# supplies.net
KiCad netlist of a schematic drawn in Altium Designer
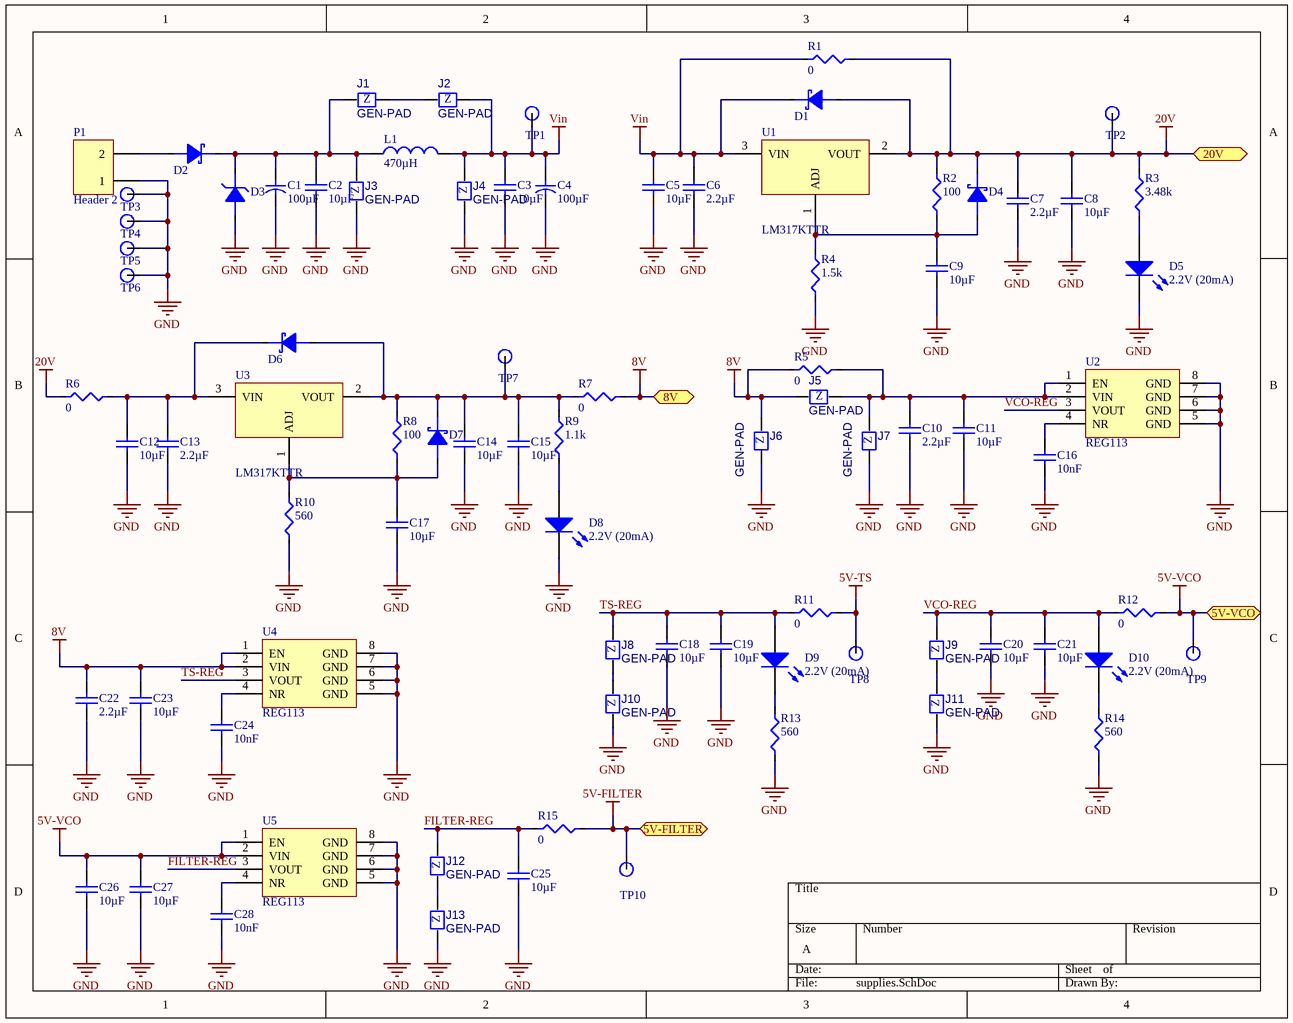
[diagram p0: supplies.SchDoc]

(export (version "E")
  (design (tool "Eeschema 10.0.6"))
  (components
    (comp (ref "C1")
      (value "100µF")
      (footprint "Radial-SMD-8x10mm")
      (description "CAP-POL")
      (fields (field (name "EE PART NUMBER") "EE-CAP-00001") (field (name "VOLTAGE") "50V"))
      (libsource (lib "EE") (part "CAP-POL"))
    )
    (comp (ref "C2")
      (value "10µF")
      (footprint "C0805-1.25MM")
      (description "Capacitor")
      (fields (field (name "EE PART NUMBER") "EE-CAP-00002") (field (name "VOLTAGE") "35V"))
      (libsource (lib "EE") (part "CAP"))
    )
    (comp (ref "C3")
      (value "10µF")
      (footprint "C0805-1.25MM")
      (description "Capacitor")
      (fields (field (name "EE PART NUMBER") "EE-CAP-00002") (field (name "VOLTAGE") "35V"))
      (libsource (lib "EE") (part "CAP"))
    )
    (comp (ref "C4")
      (value "100µF")
      (footprint "Radial-SMD-8x10mm")
      (description "CAP-POL")
      (fields (field (name "EE PART NUMBER") "EE-CAP-00001") (field (name "VOLTAGE") "50V"))
      (libsource (lib "EE") (part "CAP-POL"))
    )
    (comp (ref "C5")
      (value "10µF")
      (footprint "C0805-1.25MM")
      (description "Capacitor")
      (fields (field (name "EE PART NUMBER") "EE-CAP-00002") (field (name "VOLTAGE") "35V"))
      (libsource (lib "EE") (part "CAP"))
    )
    (comp (ref "C6")
      (value "2.2µF")
      (footprint "0402-0.55mm")
      (description "Capacitor")
      (fields (field (name "EE PART NUMBER") "EE-CAP-00003") (field (name "VOLTAGE") "35V"))
      (libsource (lib "EE") (part "CAP"))
    )
    (comp (ref "C7")
      (value "2.2µF")
      (footprint "0402-0.55mm")
      (description "Capacitor")
      (fields (field (name "EE PART NUMBER") "EE-CAP-00003") (field (name "VOLTAGE") "35V"))
      (libsource (lib "EE") (part "CAP"))
    )
    (comp (ref "C8")
      (value "10µF")
      (footprint "C0805-1.25MM")
      (description "Capacitor")
      (fields (field (name "EE PART NUMBER") "EE-CAP-00002") (field (name "VOLTAGE") "35V"))
      (libsource (lib "EE") (part "CAP"))
    )
    (comp (ref "C9")
      (value "10µF")
      (footprint "C0805-1.25MM")
      (description "Capacitor")
      (fields (field (name "EE PART NUMBER") "EE-CAP-00002") (field (name "VOLTAGE") "35V"))
      (libsource (lib "EE") (part "CAP"))
    )
    (comp (ref "C10")
      (value "2.2µF")
      (footprint "0402-0.55mm")
      (description "Capacitor")
      (fields (field (name "EE PART NUMBER") "EE-CAP-00003") (field (name "VOLTAGE") "35V"))
      (libsource (lib "EE") (part "CAP"))
    )
    (comp (ref "C11")
      (value "10µF")
      (footprint "C0805-1.25MM")
      (description "Capacitor")
      (fields (field (name "EE PART NUMBER") "EE-CAP-00002") (field (name "VOLTAGE") "35V"))
      (libsource (lib "EE") (part "CAP"))
    )
    (comp (ref "C12")
      (value "10µF")
      (footprint "C0805-1.25MM")
      (description "Capacitor")
      (fields (field (name "EE PART NUMBER") "EE-CAP-00002") (field (name "VOLTAGE") "35V"))
      (libsource (lib "EE") (part "CAP"))
    )
    (comp (ref "C13")
      (value "2.2µF")
      (footprint "0402-0.55mm")
      (description "Capacitor")
      (fields (field (name "EE PART NUMBER") "EE-CAP-00003") (field (name "VOLTAGE") "35V"))
      (libsource (lib "EE") (part "CAP"))
    )
    (comp (ref "C14")
      (value "10µF")
      (footprint "0402-0.55mm")
      (description "Capacitor")
      (fields (field (name "EE PART NUMBER") "EE-CAP-00009") (field (name "VOLTAGE") "10V"))
      (libsource (lib "EE") (part "CAP"))
    )
    (comp (ref "C15")
      (value "10µF")
      (footprint "0402-0.55mm")
      (description "Capacitor")
      (fields (field (name "EE PART NUMBER") "EE-CAP-00009") (field (name "VOLTAGE") "10V"))
      (libsource (lib "EE") (part "CAP"))
    )
    (comp (ref "C16")
      (value "10nF")
      (footprint "C0805-1.25MM")
      (description "Capacitor")
      (fields (field (name "EE PART NUMBER") "EE-CAP-00010") (field (name "VOLTAGE") "50V"))
      (libsource (lib "EE") (part "CAP"))
    )
    (comp (ref "C17")
      (value "10µF")
      (footprint "C0805-1.25MM")
      (description "Capacitor")
      (fields (field (name "EE PART NUMBER") "EE-CAP-00002") (field (name "VOLTAGE") "35V"))
      (libsource (lib "EE") (part "CAP"))
    )
    (comp (ref "C18")
      (value "10µF")
      (footprint "0402-0.55mm")
      (description "Capacitor")
      (fields (field (name "EE PART NUMBER") "EE-CAP-00004") (field (name "VOLTAGE") "10V"))
      (libsource (lib "EE") (part "CAP"))
    )
    (comp (ref "C19")
      (value "10µF")
      (footprint "0402-0.55mm")
      (description "Capacitor")
      (fields (field (name "EE PART NUMBER") "EE-CAP-00004") (field (name "VOLTAGE") "10V"))
      (libsource (lib "EE") (part "CAP"))
    )
    (comp (ref "C20")
      (value "10µF")
      (footprint "0402-0.55mm")
      (description "Capacitor")
      (fields (field (name "EE PART NUMBER") "EE-CAP-00004") (field (name "VOLTAGE") "10V"))
      (libsource (lib "EE") (part "CAP"))
    )
    (comp (ref "C21")
      (value "10µF")
      (footprint "0402-0.55mm")
      (description "Capacitor")
      (fields (field (name "EE PART NUMBER") "EE-CAP-00004") (field (name "VOLTAGE") "10V"))
      (libsource (lib "EE") (part "CAP"))
    )
    (comp (ref "C22")
      (value "2.2µF")
      (footprint "0402-0.55mm")
      (description "Capacitor")
      (fields (field (name "EE PART NUMBER") "EE-CAP-00003") (field (name "VOLTAGE") "35V"))
      (libsource (lib "EE") (part "CAP"))
    )
    (comp (ref "C23")
      (value "10µF")
      (footprint "C0805-1.25MM")
      (description "Capacitor")
      (fields (field (name "EE PART NUMBER") "EE-CAP-00002") (field (name "VOLTAGE") "35V"))
      (libsource (lib "EE") (part "CAP"))
    )
    (comp (ref "C24")
      (value "10nF")
      (footprint "C0805-1.25MM")
      (description "Capacitor")
      (fields (field (name "EE PART NUMBER") "EE-CAP-00010") (field (name "VOLTAGE") "50V"))
      (libsource (lib "EE") (part "CAP"))
    )
    (comp (ref "C25")
      (value "10µF")
      (footprint "0402-0.55mm")
      (description "Capacitor")
      (fields (field (name "EE PART NUMBER") "EE-CAP-00004") (field (name "VOLTAGE") "10V"))
      (libsource (lib "EE") (part "CAP"))
    )
    (comp (ref "C26")
      (value "10µF")
      (footprint "0402-0.55mm")
      (description "Capacitor")
      (fields (field (name "EE PART NUMBER") "EE-CAP-00004") (field (name "VOLTAGE") "10V"))
      (libsource (lib "EE") (part "CAP"))
    )
    (comp (ref "C27")
      (value "10µF")
      (footprint "0402-0.55mm")
      (description "Capacitor")
      (fields (field (name "EE PART NUMBER") "EE-CAP-00004") (field (name "VOLTAGE") "10V"))
      (libsource (lib "EE") (part "CAP"))
    )
    (comp (ref "C28")
      (value "10nF")
      (footprint "C0805-1.25MM")
      (description "Capacitor")
      (fields (field (name "EE PART NUMBER") "EE-CAP-00010") (field (name "VOLTAGE") "50V"))
      (libsource (lib "EE") (part "CAP"))
    )
    (comp (ref "D1")
      (value "SCHOTTKY")
      (footprint "SOD-123f")
      (description "Schottky Diode")
      (fields (field (name "EE PART NUMBER") "EE-DIODE-00002") (field (name "VOLTAGE") "30V"))
      (libsource (lib "EE") (part "SCHOTTKY"))
    )
    (comp (ref "D2")
      (value "SCHOTTKY")
      (footprint "SOD-123f:SOD-123f")
      (description "Schottky Diode")
      (fields (field (name "EE PART NUMBER") "EE-DIODE-00002") (field (name "VOLTAGE") "30V"))
      (libsource (lib "EE") (part "SCHOTTKY"))
    )
    (comp (ref "D3")
      (value "ZENER")
      (footprint "DO-214AA")
      (fields
        (field (name "EE PART NUMBER") "EE-DIODE-00004")
        (field (name "VOLTAGE") "25V")
        (field (name "MANUFACTURER") "Micro")
      )
      (libsource (lib "EE") (part "ZENER"))
    )
    (comp (ref "D4")
      (value "SCHOTTKY")
      (footprint "SOD-123f:SOD-123f")
      (description "Schottky Diode")
      (fields (field (name "EE PART NUMBER") "EE-DIODE-00002") (field (name "VOLTAGE") "30V"))
      (libsource (lib "EE") (part "SCHOTTKY"))
    )
    (comp (ref "D5")
      (value "2.2V (20mA)")
      (footprint "0805-LED")
      (description "LED")
      (fields (field (name "EE PART NUMBER") "EE-DIODE-00003") (field (name "VOLTAGE") "2.2V"))
      (libsource (lib "EE") (part "LED"))
    )
    (comp (ref "D6")
      (value "SCHOTTKY")
      (footprint "SOD-123f")
      (description "Schottky Diode")
      (fields (field (name "EE PART NUMBER") "EE-DIODE-00002") (field (name "VOLTAGE") "30V"))
      (libsource (lib "EE") (part "SCHOTTKY"))
    )
    (comp (ref "D7")
      (value "SCHOTTKY")
      (footprint "SOD-123f")
      (description "Schottky Diode")
      (fields (field (name "EE PART NUMBER") "EE-DIODE-00002") (field (name "VOLTAGE") "30V"))
      (libsource (lib "EE") (part "SCHOTTKY"))
    )
    (comp (ref "D8")
      (value "2.2V (20mA)")
      (footprint "0805-LED")
      (description "LED")
      (fields (field (name "EE PART NUMBER") "EE-DIODE-00003") (field (name "VOLTAGE") "2.2V"))
      (libsource (lib "EE") (part "LED"))
    )
    (comp (ref "D9")
      (value "2.2V (20mA)")
      (footprint "0805-LED")
      (description "LED")
      (fields (field (name "EE PART NUMBER") "EE-DIODE-00003") (field (name "VOLTAGE") "2.2V"))
      (libsource (lib "EE") (part "LED"))
    )
    (comp (ref "D10")
      (value "2.2V (20mA)")
      (footprint "0805-LED")
      (description "LED")
      (fields (field (name "EE PART NUMBER") "EE-DIODE-00003") (field (name "VOLTAGE") "2.2V"))
      (libsource (lib "EE") (part "LED"))
    )
    (comp (ref "J1")
      (value "GEN-PAD")
      (footprint "0805-DNP")
      (description "Generic Component")
      (fields (field (name "EE PART NUMBER") "EE-GEN-00001"))
      (libsource (lib "EE") (part "GEN-PAD"))
    )
    (comp (ref "J2")
      (value "GEN-PAD")
      (footprint "0805-DNP")
      (description "Generic Component")
      (fields (field (name "EE PART NUMBER") "EE-GEN-00001"))
      (libsource (lib "EE") (part "GEN-PAD"))
    )
    (comp (ref "J3")
      (value "GEN-PAD")
      (footprint "0805-DNP")
      (description "Generic Component")
      (fields (field (name "EE PART NUMBER") "EE-GEN-00001"))
      (libsource (lib "EE") (part "GEN-PAD"))
    )
    (comp (ref "J4")
      (value "GEN-PAD")
      (footprint "0805-DNP")
      (description "Generic Component")
      (fields (field (name "EE PART NUMBER") "EE-GEN-00001"))
      (libsource (lib "EE") (part "GEN-PAD"))
    )
    (comp (ref "J5")
      (value "GEN-PAD")
      (footprint "0805-DNP")
      (description "Generic Component")
      (fields (field (name "EE PART NUMBER") "EE-GEN-00001"))
      (libsource (lib "EE") (part "GEN-PAD"))
    )
    (comp (ref "J6")
      (value "GEN-PAD")
      (footprint "0805-DNP")
      (description "Generic Component")
      (fields (field (name "EE PART NUMBER") "EE-GEN-00001"))
      (libsource (lib "EE") (part "GEN-PAD"))
    )
    (comp (ref "J7")
      (value "GEN-PAD")
      (footprint "0805-DNP")
      (description "Generic Component")
      (fields (field (name "EE PART NUMBER") "EE-GEN-00001"))
      (libsource (lib "EE") (part "GEN-PAD"))
    )
    (comp (ref "J8")
      (value "GEN-PAD")
      (footprint "0805-DNP")
      (description "Generic Component")
      (fields (field (name "EE PART NUMBER") "EE-GEN-00001"))
      (libsource (lib "EE") (part "GEN-PAD"))
    )
    (comp (ref "J9")
      (value "GEN-PAD")
      (footprint "0805-DNP")
      (description "Generic Component")
      (fields (field (name "EE PART NUMBER") "EE-GEN-00001"))
      (libsource (lib "EE") (part "GEN-PAD"))
    )
    (comp (ref "J10")
      (value "GEN-PAD")
      (footprint "0805-DNP")
      (description "Generic Component")
      (fields (field (name "EE PART NUMBER") "EE-GEN-00001"))
      (libsource (lib "EE") (part "GEN-PAD"))
    )
    (comp (ref "J11")
      (value "GEN-PAD")
      (footprint "0805-DNP")
      (description "Generic Component")
      (fields (field (name "EE PART NUMBER") "EE-GEN-00001"))
      (libsource (lib "EE") (part "GEN-PAD"))
    )
    (comp (ref "J12")
      (value "GEN-PAD")
      (footprint "0805-DNP")
      (description "Generic Component")
      (fields (field (name "EE PART NUMBER") "EE-GEN-00001"))
      (libsource (lib "EE") (part "GEN-PAD"))
    )
    (comp (ref "J13")
      (value "GEN-PAD")
      (footprint "0805-DNP")
      (description "Generic Component")
      (fields (field (name "EE PART NUMBER") "EE-GEN-00001"))
      (libsource (lib "EE") (part "GEN-PAD"))
    )
    (comp (ref "L1")
      (value "470µH")
      (footprint "7447709471")
      (description "Inductor")
      (fields (field (name "EE PART NUMBER") "EE-L-00002") (field (name "TOLERANCE") "±20%"))
      (libsource (lib "EE") (part "L"))
    )
    (comp (ref "P1")
      (value "Header 2")
      (footprint "HDR1X2")
      (fields
        (field (name "EM PART NUMBER") "EM-CON-00012")
        (field (name "MANUFACTURER") "3M")
        (field (name "MANUFACTURER PART NUMBER") "961102-6404-AR")
      )
      (libsource (lib "EM") (part "HDR-2"))
    )
    (comp (ref "R1")
      (value "0")
      (footprint "0805-0.45MM")
      (fields
        (field (name "EM PART NUMBER") "EM-RES-01617")
        (field (name "POWER") "0.33W")
        (field (name "MANUFACTURER") "Vishay")
      )
      (libsource (lib "EM") (part "RES"))
    )
    (comp (ref "R2")
      (value "100")
      (footprint "0805-0.45MM")
      (fields
        (field (name "EM PART NUMBER") "EM-RES-01370")
        (field (name "TOLERANCE") "1%")
        (field (name "POWER") "0.125W")
      )
      (libsource (lib "EM") (part "RES"))
    )
    (comp (ref "R3")
      (value "3.48k")
      (footprint "0805-0.45MM")
      (fields
        (field (name "EM PART NUMBER") "EM-RES-01196")
        (field (name "TOLERANCE") "1%")
        (field (name "POWER") "0.125W")
      )
      (libsource (lib "EM") (part "RES"))
    )
    (comp (ref "R4")
      (value "1.5k")
      (footprint "0805-0.45MM")
      (fields
        (field (name "EM PART NUMBER") "EM-RES-01238")
        (field (name "TOLERANCE") "1%")
        (field (name "POWER") "0.125W")
      )
      (libsource (lib "EM") (part "RES"))
    )
    (comp (ref "R5")
      (value "0")
      (footprint "0805-0.45MM")
      (fields
        (field (name "EM PART NUMBER") "EM-RES-01617")
        (field (name "POWER") "0.33W")
        (field (name "MANUFACTURER") "Vishay")
      )
      (libsource (lib "EM") (part "RES"))
    )
    (comp (ref "R6")
      (value "0")
      (footprint "0805-0.45MM")
      (fields
        (field (name "EM PART NUMBER") "EM-RES-01617")
        (field (name "POWER") "0.33W")
        (field (name "MANUFACTURER") "Vishay")
      )
      (libsource (lib "EM") (part "RES"))
    )
    (comp (ref "R7")
      (value "0")
      (footprint "0805-0.45MM")
      (fields
        (field (name "EM PART NUMBER") "EM-RES-01617")
        (field (name "POWER") "0.33W")
        (field (name "MANUFACTURER") "Vishay")
      )
      (libsource (lib "EM") (part "RES"))
    )
    (comp (ref "R8")
      (value "100")
      (footprint "0805-0.45MM")
      (fields
        (field (name "EM PART NUMBER") "EM-RES-01370")
        (field (name "TOLERANCE") "1%")
        (field (name "POWER") "0.125W")
      )
      (libsource (lib "EM") (part "RES"))
    )
    (comp (ref "R9")
      (value "1.1k")
      (footprint "0805-0.45MM")
      (fields
        (field (name "EM PART NUMBER") "EM-RES-01252")
        (field (name "TOLERANCE") "1%")
        (field (name "POWER") "0.125W")
      )
      (libsource (lib "EM") (part "RES"))
    )
    (comp (ref "R10")
      (value "560")
      (footprint "0805-0.45MM")
      (fields
        (field (name "EM PART NUMBER") "EM-RES-01285")
        (field (name "TOLERANCE") "1%")
        (field (name "POWER") "0.125W")
      )
      (libsource (lib "EM") (part "RES"))
    )
    (comp (ref "R11")
      (value "0")
      (footprint "0805-0.45MM")
      (fields
        (field (name "EM PART NUMBER") "EM-RES-01617")
        (field (name "POWER") "0.33W")
        (field (name "MANUFACTURER") "Vishay")
      )
      (libsource (lib "EM") (part "RES"))
    )
    (comp (ref "R12")
      (value "0")
      (footprint "0805-0.45MM")
      (fields
        (field (name "EM PART NUMBER") "EM-RES-01617")
        (field (name "POWER") "0.33W")
        (field (name "MANUFACTURER") "Vishay")
      )
      (libsource (lib "EM") (part "RES"))
    )
    (comp (ref "R13")
      (value "560")
      (footprint "0805-0.45MM")
      (fields
        (field (name "EM PART NUMBER") "EM-RES-01285")
        (field (name "TOLERANCE") "1%")
        (field (name "POWER") "0.125W")
      )
      (libsource (lib "EM") (part "RES"))
    )
    (comp (ref "R14")
      (value "560")
      (footprint "0805-0.45MM")
      (fields
        (field (name "EM PART NUMBER") "EM-RES-01285")
        (field (name "TOLERANCE") "1%")
        (field (name "POWER") "0.125W")
      )
      (libsource (lib "EM") (part "RES"))
    )
    (comp (ref "R15")
      (value "0")
      (footprint "0805-0.45MM")
      (fields
        (field (name "EM PART NUMBER") "EM-RES-01617")
        (field (name "POWER") "0.33W")
        (field (name "MANUFACTURER") "Vishay")
      )
      (libsource (lib "EM") (part "RES"))
    )
    (comp (ref "TP1")
      (value "TP-LOOP")
      (footprint "TP-LOOP")
      (fields (field (name "EM PART NUMBER") "EM-TP-00006"))
      (libsource (lib "EM") (part "TP-LOOP"))
    )
    (comp (ref "TP2")
      (value "TP-LOOP")
      (footprint "TP-LOOP")
      (fields (field (name "EM PART NUMBER") "EM-TP-00006"))
      (libsource (lib "EM") (part "TP-LOOP"))
    )
    (comp (ref "TP3")
      (value "TP-LOOP")
      (footprint "TP-LOOP")
      (fields (field (name "EM PART NUMBER") "EM-TP-00006"))
      (libsource (lib "EM") (part "TP-LOOP"))
    )
    (comp (ref "TP4")
      (value "TP-LOOP")
      (footprint "TP-LOOP")
      (fields (field (name "EM PART NUMBER") "EM-TP-00006"))
      (libsource (lib "EM") (part "TP-LOOP"))
    )
    (comp (ref "TP5")
      (value "TP-LOOP")
      (footprint "TP-LOOP")
      (fields (field (name "EM PART NUMBER") "EM-TP-00006"))
      (libsource (lib "EM") (part "TP-LOOP"))
    )
    (comp (ref "TP6")
      (value "TP-LOOP")
      (footprint "TP-LOOP")
      (fields (field (name "EM PART NUMBER") "EM-TP-00006"))
      (libsource (lib "EM") (part "TP-LOOP"))
    )
    (comp (ref "TP7")
      (value "TP-LOOP")
      (footprint "TP-LOOP")
      (fields (field (name "EM PART NUMBER") "EM-TP-00006"))
      (libsource (lib "EM") (part "TP-LOOP"))
    )
    (comp (ref "TP8")
      (value "TP-LOOP")
      (footprint "TP-LOOP")
      (fields (field (name "EM PART NUMBER") "EM-TP-00006"))
      (libsource (lib "EM") (part "TP-LOOP"))
    )
    (comp (ref "TP9")
      (value "TP-LOOP")
      (footprint "TP-LOOP")
      (fields (field (name "EM PART NUMBER") "EM-TP-00006"))
      (libsource (lib "EM") (part "TP-LOOP"))
    )
    (comp (ref "TP10")
      (value "TP-LOOP")
      (footprint "TP-LOOP")
      (fields (field (name "EM PART NUMBER") "EM-TP-00006"))
      (libsource (lib "EM") (part "TP-LOOP"))
    )
    (comp (ref "U1")
      (value "LM317KTTR")
      (footprint "TO-263-4")
      (fields (field (name "EE PART NUMBER") "EE-VREG-00004") (field (name "MANUFACTURER") "TI"))
      (libsource (lib "EE") (part "LM317"))
    )
    (comp (ref "U2")
      (value "REG113")
      (footprint "MSOP8")
      (fields
        (field (name "EE PART NUMBER") "EE-VREG-00002")
        (field (name "MANUFACTURER") "TI")
        (field (name "MANUFACTURER PART NUMBER") "REG113EA-5/250")
      )
      (libsource (lib "EE") (part "REG113"))
    )
    (comp (ref "U3")
      (value "LM317KTTR")
      (footprint "TO-263-4")
      (fields (field (name "EE PART NUMBER") "EE-VREG-00004") (field (name "MANUFACTURER") "TI"))
      (libsource (lib "EE") (part "LM317"))
    )
    (comp (ref "U4")
      (value "REG113")
      (footprint "MSOP8")
      (fields
        (field (name "EE PART NUMBER") "EE-VREG-00002")
        (field (name "MANUFACTURER") "TI")
        (field (name "MANUFACTURER PART NUMBER") "REG113EA-5/250")
      )
      (libsource (lib "EE") (part "REG113"))
    )
    (comp (ref "U5")
      (value "REG113")
      (footprint "MSOP8")
      (fields
        (field (name "EE PART NUMBER") "EE-VREG-00003")
        (field (name "MANUFACTURER") "TI")
        (field (name "MANUFACTURER PART NUMBER") "REG113EA-2.5/2K5")
      )
      (libsource (lib "EE") (part "REG113"))
    )
  )
  (nets
    (net (code "1") (name "/FILTER-REG") (class "Default")
      (node (ref "C25") (pin "1") (pinfunction "1_1") (pintype "passive"))
      (node (ref "J12") (pin "1") (pinfunction "1_1") (pintype "passive"))
      (node (ref "R15") (pin "1") (pinfunction "1_1") (pintype "passive"))
      (node (ref "U5") (pin "3") (pinfunction "VOUT_3") (pintype "passive"))
    )
    (net (code "2") (name "/TS-REG") (class "Default")
      (node (ref "C18") (pin "2") (pinfunction "2_2") (pintype "passive"))
      (node (ref "C19") (pin "2") (pinfunction "2_2") (pintype "passive"))
      (node (ref "D9") (pin "A") (pinfunction "A_A") (pintype "passive"))
      (node (ref "J8") (pin "1") (pinfunction "1_1") (pintype "passive"))
      (node (ref "R11") (pin "1") (pinfunction "1_1") (pintype "passive"))
      (node (ref "U4") (pin "3") (pinfunction "VOUT_3") (pintype "passive"))
    )
    (net (code "3") (name "/VCO-REG") (class "Default")
      (node (ref "C20") (pin "2") (pinfunction "2_2") (pintype "passive"))
      (node (ref "C21") (pin "2") (pinfunction "2_2") (pintype "passive"))
      (node (ref "D10") (pin "A") (pinfunction "A_A") (pintype "passive"))
      (node (ref "J9") (pin "1") (pinfunction "1_1") (pintype "passive"))
      (node (ref "R12") (pin "2") (pinfunction "2_2") (pintype "passive"))
      (node (ref "U2") (pin "3") (pinfunction "VOUT_3") (pintype "passive"))
    )
    (net (code "4") (name "5V-FILTER") (class "Default")
      (node (ref "R15") (pin "2") (pinfunction "2_2") (pintype "passive"))
      (node (ref "TP10") (pin "0") (pinfunction "0_0") (pintype "passive"))
    )
    (net (code "5") (name "5V-TS") (class "Default")
      (node (ref "R11") (pin "2") (pinfunction "2_2") (pintype "passive"))
      (node (ref "TP8") (pin "0") (pinfunction "0_0") (pintype "passive"))
    )
    (net (code "6") (name "5V-VCO") (class "Default")
      (node (ref "C26") (pin "1") (pinfunction "1_1") (pintype "passive"))
      (node (ref "C27") (pin "1") (pinfunction "1_1") (pintype "passive"))
      (node (ref "R12") (pin "1") (pinfunction "1_1") (pintype "passive"))
      (node (ref "TP9") (pin "0") (pinfunction "0_0") (pintype "passive"))
      (node (ref "U5") (pin "1") (pinfunction "EN_1") (pintype "passive"))
      (node (ref "U5") (pin "2") (pinfunction "VIN_2") (pintype "passive"))
    )
    (net (code "7") (name "8V") (class "Default")
      (node (ref "C22") (pin "2") (pinfunction "2_2") (pintype "passive"))
      (node (ref "C23") (pin "2") (pinfunction "2_2") (pintype "passive"))
      (node (ref "J5") (pin "2") (pinfunction "2_2") (pintype "passive"))
      (node (ref "J6") (pin "1") (pinfunction "1_1") (pintype "passive"))
      (node (ref "R5") (pin "1") (pinfunction "1_1") (pintype "passive"))
      (node (ref "R7") (pin "2") (pinfunction "2_2") (pintype "passive"))
      (node (ref "U4") (pin "1") (pinfunction "EN_1") (pintype "passive"))
      (node (ref "U4") (pin "2") (pinfunction "VIN_2") (pintype "passive"))
    )
    (net (code "8") (name "20V") (class "Default")
      (node (ref "C7") (pin "2") (pinfunction "2_2") (pintype "passive"))
      (node (ref "C8") (pin "2") (pinfunction "2_2") (pintype "passive"))
      (node (ref "D1") (pin "A") (pinfunction "A_A") (pintype "passive"))
      (node (ref "D4") (pin "C") (pinfunction "C_C") (pintype "passive"))
      (node (ref "R1") (pin "2") (pinfunction "2_2") (pintype "passive"))
      (node (ref "R2") (pin "2") (pinfunction "2_2") (pintype "passive"))
      (node (ref "R3") (pin "2") (pinfunction "2_2") (pintype "passive"))
      (node (ref "R6") (pin "1") (pinfunction "1_1") (pintype "passive"))
      (node (ref "TP2") (pin "0") (pinfunction "0_0") (pintype "passive"))
      (node (ref "U1") (pin "2") (pinfunction "VOUT_2") (pintype "power_in"))
    )
    (net (code "9") (name "GND") (class "Default")
      (node (ref "C1") (pin "1") (pinfunction "1_1") (pintype "passive"))
      (node (ref "C10") (pin "1") (pinfunction "1_1") (pintype "passive"))
      (node (ref "C11") (pin "1") (pinfunction "1_1") (pintype "passive"))
      (node (ref "C12") (pin "1") (pinfunction "1_1") (pintype "passive"))
      (node (ref "C13") (pin "1") (pinfunction "1_1") (pintype "passive"))
      (node (ref "C14") (pin "1") (pinfunction "1_1") (pintype "passive"))
      (node (ref "C15") (pin "1") (pinfunction "1_1") (pintype "passive"))
      (node (ref "C16") (pin "1") (pinfunction "1_1") (pintype "passive"))
      (node (ref "C17") (pin "1") (pinfunction "1_1") (pintype "passive"))
      (node (ref "C18") (pin "1") (pinfunction "1_1") (pintype "passive"))
      (node (ref "C19") (pin "1") (pinfunction "1_1") (pintype "passive"))
      (node (ref "C2") (pin "1") (pinfunction "1_1") (pintype "passive"))
      (node (ref "C20") (pin "1") (pinfunction "1_1") (pintype "passive"))
      (node (ref "C21") (pin "1") (pinfunction "1_1") (pintype "passive"))
      (node (ref "C22") (pin "1") (pinfunction "1_1") (pintype "passive"))
      (node (ref "C23") (pin "1") (pinfunction "1_1") (pintype "passive"))
      (node (ref "C24") (pin "1") (pinfunction "1_1") (pintype "passive"))
      (node (ref "C25") (pin "2") (pinfunction "2_2") (pintype "passive"))
      (node (ref "C26") (pin "2") (pinfunction "2_2") (pintype "passive"))
      (node (ref "C27") (pin "2") (pinfunction "2_2") (pintype "passive"))
      (node (ref "C28") (pin "1") (pinfunction "1_1") (pintype "passive"))
      (node (ref "C3") (pin "1") (pinfunction "1_1") (pintype "passive"))
      (node (ref "C4") (pin "1") (pinfunction "1_1") (pintype "passive"))
      (node (ref "C5") (pin "1") (pinfunction "1_1") (pintype "passive"))
      (node (ref "C6") (pin "1") (pinfunction "1_1") (pintype "passive"))
      (node (ref "C7") (pin "1") (pinfunction "1_1") (pintype "passive"))
      (node (ref "C8") (pin "1") (pinfunction "1_1") (pintype "passive"))
      (node (ref "C9") (pin "1") (pinfunction "1_1") (pintype "passive"))
      (node (ref "D3") (pin "1") (pinfunction "A_1") (pintype "passive"))
      (node (ref "D5") (pin "C") (pinfunction "C_C") (pintype "passive"))
      (node (ref "D8") (pin "C") (pinfunction "C_C") (pintype "passive"))
      (node (ref "J10") (pin "2") (pinfunction "2_2") (pintype "passive"))
      (node (ref "J11") (pin "2") (pinfunction "2_2") (pintype "passive"))
      (node (ref "J13") (pin "2") (pinfunction "2_2") (pintype "passive"))
      (node (ref "J3") (pin "2") (pinfunction "2_2") (pintype "passive"))
      (node (ref "J4") (pin "2") (pinfunction "2_2") (pintype "passive"))
      (node (ref "J6") (pin "2") (pinfunction "2_2") (pintype "passive"))
      (node (ref "J7") (pin "2") (pinfunction "2_2") (pintype "passive"))
      (node (ref "P1") (pin "1") (pinfunction "1_1") (pintype "passive"))
      (node (ref "R10") (pin "1") (pinfunction "1_1") (pintype "passive"))
      (node (ref "R13") (pin "1") (pinfunction "1_1") (pintype "passive"))
      (node (ref "R14") (pin "1") (pinfunction "1_1") (pintype "passive"))
      (node (ref "R4") (pin "1") (pinfunction "1_1") (pintype "passive"))
      (node (ref "TP3") (pin "0") (pinfunction "0_0") (pintype "passive"))
      (node (ref "TP4") (pin "0") (pinfunction "0_0") (pintype "passive"))
      (node (ref "TP5") (pin "0") (pinfunction "0_0") (pintype "passive"))
      (node (ref "TP6") (pin "0") (pinfunction "0_0") (pintype "passive"))
      (node (ref "U2") (pin "5") (pinfunction "GND_5") (pintype "passive"))
      (node (ref "U2") (pin "6") (pinfunction "GND_6") (pintype "passive"))
      (node (ref "U2") (pin "7") (pinfunction "GND_7") (pintype "passive"))
      (node (ref "U2") (pin "8") (pinfunction "GND_8") (pintype "passive"))
      (node (ref "U4") (pin "5") (pinfunction "GND_5") (pintype "passive"))
      (node (ref "U4") (pin "6") (pinfunction "GND_6") (pintype "passive"))
      (node (ref "U4") (pin "7") (pinfunction "GND_7") (pintype "passive"))
      (node (ref "U4") (pin "8") (pinfunction "GND_8") (pintype "passive"))
      (node (ref "U5") (pin "5") (pinfunction "GND_5") (pintype "passive"))
      (node (ref "U5") (pin "6") (pinfunction "GND_6") (pintype "passive"))
      (node (ref "U5") (pin "7") (pinfunction "GND_7") (pintype "passive"))
      (node (ref "U5") (pin "8") (pinfunction "GND_8") (pintype "passive"))
    )
    (net (code "10") (name "Net-(D2-PadA)") (class "Default")
      (node (ref "D2") (pin "A") (pinfunction "A_A") (pintype "passive"))
      (node (ref "P1") (pin "2") (pinfunction "2_2") (pintype "passive"))
    )
    (net (code "11") (name "Net-(D3-C)") (class "Default")
      (node (ref "C1") (pin "2") (pinfunction "2_2") (pintype "passive"))
      (node (ref "C2") (pin "2") (pinfunction "2_2") (pintype "passive"))
      (node (ref "D2") (pin "C") (pinfunction "C_C") (pintype "passive"))
      (node (ref "D3") (pin "2") (pinfunction "C_2") (pintype "passive"))
      (node (ref "J1") (pin "2") (pinfunction "2_2") (pintype "passive"))
      (node (ref "J3") (pin "1") (pinfunction "1_1") (pintype "passive"))
      (node (ref "L1") (pin "1") (pinfunction "1_1") (pintype "passive"))
    )
    (net (code "12") (name "Net-(D5-PadA)") (class "Default")
      (node (ref "D5") (pin "A") (pinfunction "A_A") (pintype "passive"))
      (node (ref "R3") (pin "1") (pinfunction "1_1") (pintype "passive"))
    )
    (net (code "13") (name "Net-(D8-PadA)") (class "Default")
      (node (ref "D8") (pin "A") (pinfunction "A_A") (pintype "passive"))
      (node (ref "R9") (pin "1") (pinfunction "1_1") (pintype "passive"))
    )
    (net (code "14") (name "Net-(D9-PadC)") (class "Default")
      (node (ref "D9") (pin "C") (pinfunction "C_C") (pintype "passive"))
      (node (ref "R13") (pin "2") (pinfunction "2_2") (pintype "passive"))
    )
    (net (code "15") (name "Net-(D10-PadC)") (class "Default")
      (node (ref "D10") (pin "C") (pinfunction "C_C") (pintype "passive"))
      (node (ref "R14") (pin "2") (pinfunction "2_2") (pintype "passive"))
    )
    (net (code "16") (name "Net-(J1-Pad1)") (class "Default")
      (node (ref "J1") (pin "1") (pinfunction "1_1") (pintype "passive"))
      (node (ref "J2") (pin "2") (pinfunction "2_2") (pintype "passive"))
    )
    (net (code "17") (name "Net-(J10-Pad1)") (class "Default")
      (node (ref "J10") (pin "1") (pinfunction "1_1") (pintype "passive"))
      (node (ref "J8") (pin "2") (pinfunction "2_2") (pintype "passive"))
    )
    (net (code "18") (name "Net-(J11-Pad1)") (class "Default")
      (node (ref "J11") (pin "1") (pinfunction "1_1") (pintype "passive"))
      (node (ref "J9") (pin "2") (pinfunction "2_2") (pintype "passive"))
    )
    (net (code "19") (name "Net-(J12-Pad2)") (class "Default")
      (node (ref "J12") (pin "2") (pinfunction "2_2") (pintype "passive"))
      (node (ref "J13") (pin "1") (pinfunction "1_1") (pintype "passive"))
    )
    (net (code "20") (name "Net-(U1-ADJ)") (class "Default")
      (node (ref "C9") (pin "2") (pinfunction "2_2") (pintype "passive"))
      (node (ref "D4") (pin "A") (pinfunction "A_A") (pintype "passive"))
      (node (ref "R2") (pin "1") (pinfunction "1_1") (pintype "passive"))
      (node (ref "R4") (pin "2") (pinfunction "2_2") (pintype "passive"))
      (node (ref "U1") (pin "1") (pinfunction "ADJ_1") (pintype "power_in"))
    )
    (net (code "21") (name "Net-(U2-EN)") (class "Default")
      (node (ref "C10") (pin "2") (pinfunction "2_2") (pintype "passive"))
      (node (ref "C11") (pin "2") (pinfunction "2_2") (pintype "passive"))
      (node (ref "J5") (pin "1") (pinfunction "1_1") (pintype "passive"))
      (node (ref "J7") (pin "1") (pinfunction "1_1") (pintype "passive"))
      (node (ref "R5") (pin "2") (pinfunction "2_2") (pintype "passive"))
      (node (ref "U2") (pin "1") (pinfunction "EN_1") (pintype "passive"))
      (node (ref "U2") (pin "2") (pinfunction "VIN_2") (pintype "passive"))
    )
    (net (code "22") (name "Net-(U2-NR)") (class "Default")
      (node (ref "C16") (pin "2") (pinfunction "2_2") (pintype "passive"))
      (node (ref "U2") (pin "4") (pinfunction "NR_4") (pintype "passive"))
    )
    (net (code "23") (name "Net-(U3-ADJ)") (class "Default")
      (node (ref "C17") (pin "2") (pinfunction "2_2") (pintype "passive"))
      (node (ref "D7") (pin "A") (pinfunction "A_A") (pintype "passive"))
      (node (ref "R10") (pin "2") (pinfunction "2_2") (pintype "passive"))
      (node (ref "R8") (pin "1") (pinfunction "1_1") (pintype "passive"))
      (node (ref "U3") (pin "1") (pinfunction "ADJ_1") (pintype "power_in"))
    )
    (net (code "24") (name "Net-(U3-VIN)") (class "Default")
      (node (ref "C12") (pin "2") (pinfunction "2_2") (pintype "passive"))
      (node (ref "C13") (pin "2") (pinfunction "2_2") (pintype "passive"))
      (node (ref "D6") (pin "C") (pinfunction "C_C") (pintype "passive"))
      (node (ref "R6") (pin "2") (pinfunction "2_2") (pintype "passive"))
      (node (ref "U3") (pin "3") (pinfunction "VIN_3") (pintype "power_in"))
    )
    (net (code "25") (name "Net-(U3-VOUT)") (class "Default")
      (node (ref "C14") (pin "2") (pinfunction "2_2") (pintype "passive"))
      (node (ref "C15") (pin "2") (pinfunction "2_2") (pintype "passive"))
      (node (ref "D6") (pin "A") (pinfunction "A_A") (pintype "passive"))
      (node (ref "D7") (pin "C") (pinfunction "C_C") (pintype "passive"))
      (node (ref "R7") (pin "1") (pinfunction "1_1") (pintype "passive"))
      (node (ref "R8") (pin "2") (pinfunction "2_2") (pintype "passive"))
      (node (ref "R9") (pin "2") (pinfunction "2_2") (pintype "passive"))
      (node (ref "TP7") (pin "0") (pinfunction "0_0") (pintype "passive"))
      (node (ref "U3") (pin "2") (pinfunction "VOUT_2") (pintype "power_in"))
    )
    (net (code "26") (name "Net-(U4-NR)") (class "Default")
      (node (ref "C24") (pin "2") (pinfunction "2_2") (pintype "passive"))
      (node (ref "U4") (pin "4") (pinfunction "NR_4") (pintype "passive"))
    )
    (net (code "27") (name "Net-(U5-NR)") (class "Default")
      (node (ref "C28") (pin "2") (pinfunction "2_2") (pintype "passive"))
      (node (ref "U5") (pin "4") (pinfunction "NR_4") (pintype "passive"))
    )
    (net (code "28") (name "Vin") (class "Default")
      (node (ref "C3") (pin "2") (pinfunction "2_2") (pintype "passive"))
      (node (ref "C4") (pin "2") (pinfunction "2_2") (pintype "passive"))
      (node (ref "C5") (pin "2") (pinfunction "2_2") (pintype "passive"))
      (node (ref "C6") (pin "2") (pinfunction "2_2") (pintype "passive"))
      (node (ref "D1") (pin "C") (pinfunction "C_C") (pintype "passive"))
      (node (ref "J2") (pin "1") (pinfunction "1_1") (pintype "passive"))
      (node (ref "J4") (pin "1") (pinfunction "1_1") (pintype "passive"))
      (node (ref "L1") (pin "2") (pinfunction "2_2") (pintype "passive"))
      (node (ref "R1") (pin "1") (pinfunction "1_1") (pintype "passive"))
      (node (ref "TP1") (pin "0") (pinfunction "0_0") (pintype "passive"))
      (node (ref "U1") (pin "3") (pinfunction "VIN_3") (pintype "power_in"))
    )
  )
)
